# 24_067.net
KiCad netlist of a schematic drawn in Altium Designer
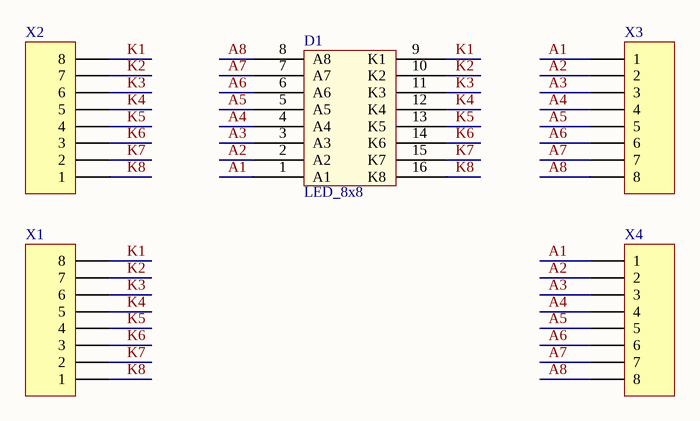
[diagram p0: 24.067.SchDoc]

(export (version "E")
  (design (tool "Eeschema 10.0.6"))
  (components
    (comp (ref "D1") (value "LED_8x8") (footprint "LED_8x8") (libsource (lib "msp_SchLib") (part "LED_8x8")))
    (comp (ref "X1")
      (value "Header 8")
      (footprint "HDR1X8")
      (description "Header, 8-Pin")
      (fields (field (name "PUBLISHER") "Altium Limited"))
      (libsource (lib "Miscellaneous Connectors") (part "Header 8"))
    )
    (comp (ref "X2")
      (value "Header 8")
      (footprint "HDR1X8")
      (description "Header, 8-Pin")
      (fields (field (name "PUBLISHER") "Altium Limited"))
      (libsource (lib "Miscellaneous Connectors") (part "Header 8"))
    )
    (comp (ref "X3")
      (value "Header 8")
      (footprint "HDR1X8")
      (description "Header, 8-Pin")
      (fields (field (name "PUBLISHER") "Altium Limited"))
      (libsource (lib "") (part "Header 8_1"))
    )
    (comp (ref "X4")
      (value "Header 8")
      (footprint "HDR1X8")
      (description "Header, 8-Pin")
      (fields (field (name "PUBLISHER") "Altium Limited"))
      (libsource (lib "") (part "Header 8_1"))
    )
  )
  (nets
    (net (code "1") (name "/A1") (class "Default")
      (node (ref "D1") (pin "1") (pinfunction "A1_1") (pintype "passive"))
      (node (ref "X3") (pin "1") (pinfunction "1_1") (pintype "passive"))
      (node (ref "X4") (pin "1") (pinfunction "1_1") (pintype "passive"))
    )
    (net (code "2") (name "/A2") (class "Default")
      (node (ref "D1") (pin "2") (pinfunction "A2_2") (pintype "passive"))
      (node (ref "X3") (pin "2") (pinfunction "2_2") (pintype "passive"))
      (node (ref "X4") (pin "2") (pinfunction "2_2") (pintype "passive"))
    )
    (net (code "3") (name "/A3") (class "Default")
      (node (ref "D1") (pin "3") (pinfunction "A3_3") (pintype "passive"))
      (node (ref "X3") (pin "3") (pinfunction "3_3") (pintype "passive"))
      (node (ref "X4") (pin "3") (pinfunction "3_3") (pintype "passive"))
    )
    (net (code "4") (name "/A4") (class "Default")
      (node (ref "D1") (pin "4") (pinfunction "A4_4") (pintype "passive"))
      (node (ref "X3") (pin "4") (pinfunction "4_4") (pintype "passive"))
      (node (ref "X4") (pin "4") (pinfunction "4_4") (pintype "passive"))
    )
    (net (code "5") (name "/A5") (class "Default")
      (node (ref "D1") (pin "5") (pinfunction "A5_5") (pintype "passive"))
      (node (ref "X3") (pin "5") (pinfunction "5_5") (pintype "passive"))
      (node (ref "X4") (pin "5") (pinfunction "5_5") (pintype "passive"))
    )
    (net (code "6") (name "/A6") (class "Default")
      (node (ref "D1") (pin "6") (pinfunction "A6_6") (pintype "passive"))
      (node (ref "X3") (pin "6") (pinfunction "6_6") (pintype "passive"))
      (node (ref "X4") (pin "6") (pinfunction "6_6") (pintype "passive"))
    )
    (net (code "7") (name "/A7") (class "Default")
      (node (ref "D1") (pin "7") (pinfunction "A7_7") (pintype "passive"))
      (node (ref "X3") (pin "7") (pinfunction "7_7") (pintype "passive"))
      (node (ref "X4") (pin "7") (pinfunction "7_7") (pintype "passive"))
    )
    (net (code "8") (name "/A8") (class "Default")
      (node (ref "D1") (pin "8") (pinfunction "A8_8") (pintype "passive"))
      (node (ref "X3") (pin "8") (pinfunction "8_8") (pintype "passive"))
      (node (ref "X4") (pin "8") (pinfunction "8_8") (pintype "passive"))
    )
    (net (code "9") (name "/K1") (class "Default")
      (node (ref "D1") (pin "9") (pinfunction "K1_9") (pintype "passive"))
      (node (ref "X1") (pin "8") (pinfunction "8_8") (pintype "passive"))
      (node (ref "X2") (pin "8") (pinfunction "8_8") (pintype "passive"))
    )
    (net (code "10") (name "/K2") (class "Default")
      (node (ref "D1") (pin "10") (pinfunction "K2_10") (pintype "passive"))
      (node (ref "X1") (pin "7") (pinfunction "7_7") (pintype "passive"))
      (node (ref "X2") (pin "7") (pinfunction "7_7") (pintype "passive"))
    )
    (net (code "11") (name "/K3") (class "Default")
      (node (ref "D1") (pin "11") (pinfunction "K3_11") (pintype "passive"))
      (node (ref "X1") (pin "6") (pinfunction "6_6") (pintype "passive"))
      (node (ref "X2") (pin "6") (pinfunction "6_6") (pintype "passive"))
    )
    (net (code "12") (name "/K4") (class "Default")
      (node (ref "D1") (pin "12") (pinfunction "K4_12") (pintype "passive"))
      (node (ref "X1") (pin "5") (pinfunction "5_5") (pintype "passive"))
      (node (ref "X2") (pin "5") (pinfunction "5_5") (pintype "passive"))
    )
    (net (code "13") (name "/K5") (class "Default")
      (node (ref "D1") (pin "13") (pinfunction "K5_13") (pintype "passive"))
      (node (ref "X1") (pin "4") (pinfunction "4_4") (pintype "passive"))
      (node (ref "X2") (pin "4") (pinfunction "4_4") (pintype "passive"))
    )
    (net (code "14") (name "/K6") (class "Default")
      (node (ref "D1") (pin "14") (pinfunction "K6_14") (pintype "passive"))
      (node (ref "X1") (pin "3") (pinfunction "3_3") (pintype "passive"))
      (node (ref "X2") (pin "3") (pinfunction "3_3") (pintype "passive"))
    )
    (net (code "15") (name "/K7") (class "Default")
      (node (ref "D1") (pin "15") (pinfunction "K7_15") (pintype "passive"))
      (node (ref "X1") (pin "2") (pinfunction "2_2") (pintype "passive"))
      (node (ref "X2") (pin "2") (pinfunction "2_2") (pintype "passive"))
    )
    (net (code "16") (name "/K8") (class "Default")
      (node (ref "D1") (pin "16") (pinfunction "K8_16") (pintype "passive"))
      (node (ref "X1") (pin "1") (pinfunction "1_1") (pintype "passive"))
      (node (ref "X2") (pin "1") (pinfunction "1_1") (pintype "passive"))
    )
  )
)
